# axoloti_micro_modular_002.net
KiCad netlist of a schematic drawn in EAGLE
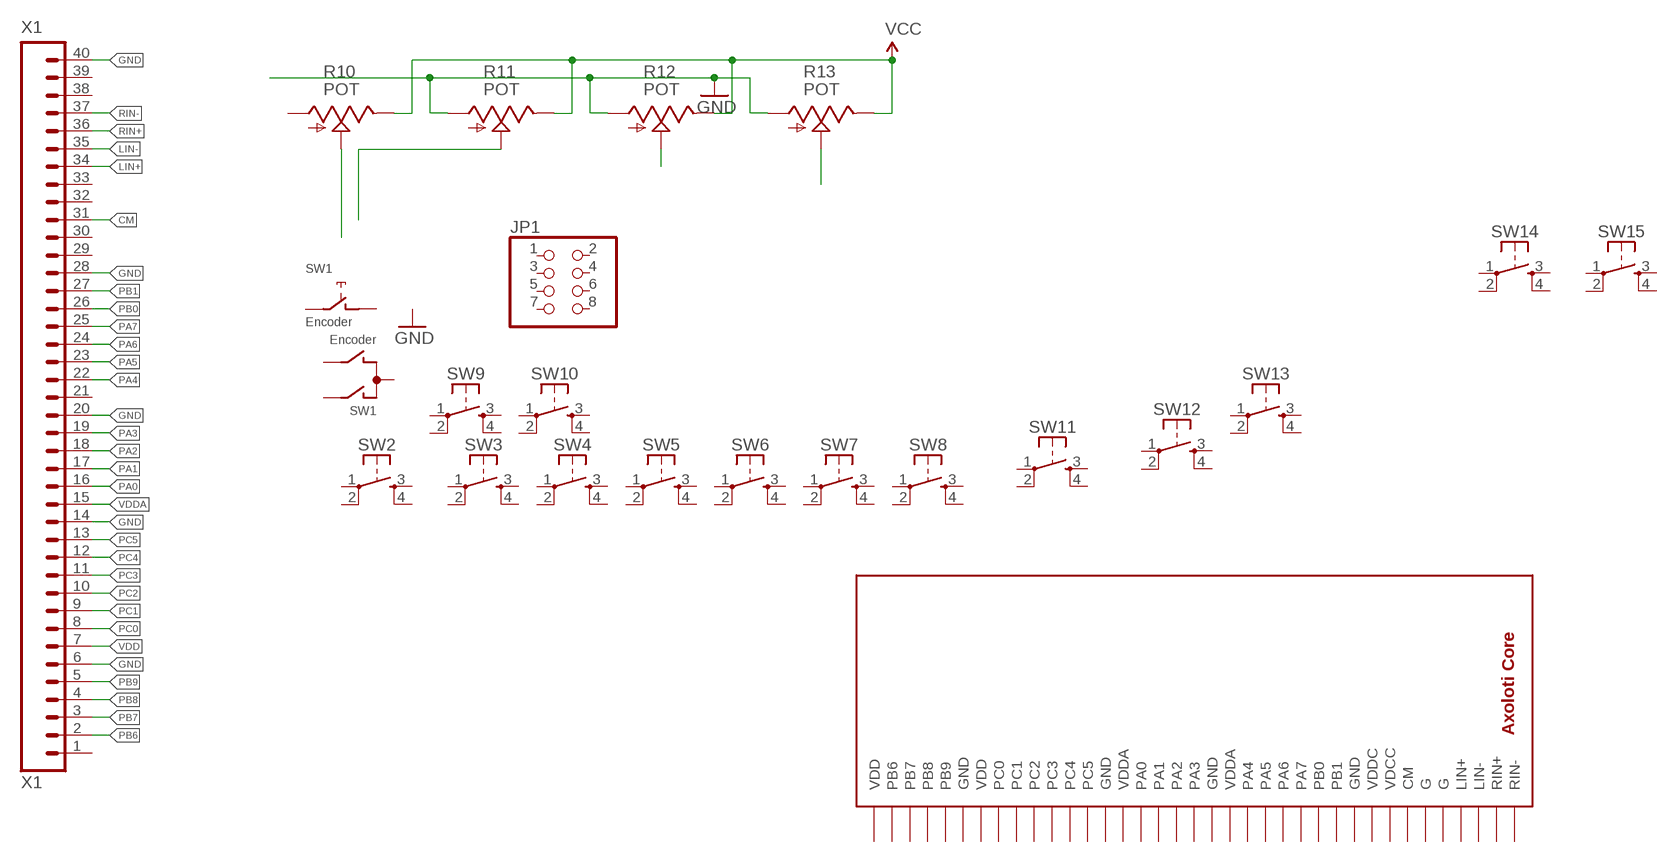
[diagram p0: schematic, sheet 1]

(export (version "E")
  (design (tool "Eeschema 10.0.6"))
  (components
    (comp (ref "JP1")
      (value "PINHD-2X4")
      (footprint "eagle-import:2X04")
      (libsource (lib "eagle-import") (part "PINHD-2X4"))
    )
    (comp (ref "R10")
      (value "POT")
      (footprint "eagle-import:ALPS_POT_SFE")
      (libsource (lib "eagle-import") (part "POT_US"))
    )
    (comp (ref "R11")
      (value "POT")
      (footprint "eagle-import:ALPS_POT_SFE")
      (libsource (lib "eagle-import") (part "POT_US"))
    )
    (comp (ref "R12")
      (value "POT")
      (footprint "eagle-import:ALPS_POT_SFE")
      (libsource (lib "eagle-import") (part "POT_US"))
    )
    (comp (ref "R13")
      (value "POT")
      (footprint "eagle-import:ALPS_POT_SFE")
      (libsource (lib "eagle-import") (part "POT_US"))
    )
    (comp (ref "SW1")
      (value "Encoder")
      (footprint "eagle-import:ALPS_EC12E_SW")
      (libsource (lib "eagle-import") (part "EC12E_SW"))
    )
    (comp (ref "SW2")
      (value "SW-TACTILE-6X6")
      (footprint "eagle-import:SW6X6")
      (libsource (lib "eagle-import") (part "SW-TACTILE-6X6"))
    )
    (comp (ref "SW3")
      (value "SW-TACTILE-6X6")
      (footprint "eagle-import:SW6X6")
      (libsource (lib "eagle-import") (part "SW-TACTILE-6X6"))
    )
    (comp (ref "SW4")
      (value "SW-TACTILE-6X6")
      (footprint "eagle-import:SW6X6")
      (libsource (lib "eagle-import") (part "SW-TACTILE-6X6"))
    )
    (comp (ref "SW5")
      (value "SW-TACTILE-6X6")
      (footprint "eagle-import:SW6X6")
      (libsource (lib "eagle-import") (part "SW-TACTILE-6X6"))
    )
    (comp (ref "SW6")
      (value "SW-TACTILE-6X6")
      (footprint "eagle-import:SW6X6")
      (libsource (lib "eagle-import") (part "SW-TACTILE-6X6"))
    )
    (comp (ref "SW7")
      (value "SW-TACTILE-6X6")
      (footprint "eagle-import:SW6X6")
      (libsource (lib "eagle-import") (part "SW-TACTILE-6X6"))
    )
    (comp (ref "SW8")
      (value "SW-TACTILE-6X6")
      (footprint "eagle-import:SW6X6")
      (libsource (lib "eagle-import") (part "SW-TACTILE-6X6"))
    )
    (comp (ref "SW9")
      (value "SW-TACTILE-6X6")
      (footprint "eagle-import:SW6X6")
      (libsource (lib "eagle-import") (part "SW-TACTILE-6X6"))
    )
    (comp (ref "SW10")
      (value "SW-TACTILE-6X6")
      (footprint "eagle-import:SW6X6")
      (libsource (lib "eagle-import") (part "SW-TACTILE-6X6"))
    )
    (comp (ref "SW11")
      (value "SW-TACTILE-6X6")
      (footprint "eagle-import:SW6X6")
      (libsource (lib "eagle-import") (part "SW-TACTILE-6X6"))
    )
    (comp (ref "SW12")
      (value "SW-TACTILE-6X6")
      (footprint "eagle-import:SW6X6")
      (libsource (lib "eagle-import") (part "SW-TACTILE-6X6"))
    )
    (comp (ref "SW13")
      (value "SW-TACTILE-6X6")
      (footprint "eagle-import:SW6X6")
      (libsource (lib "eagle-import") (part "SW-TACTILE-6X6"))
    )
    (comp (ref "SW14")
      (value "SW-TACTILE-6X6")
      (footprint "eagle-import:SW6X6")
      (libsource (lib "eagle-import") (part "SW-TACTILE-6X6"))
    )
    (comp (ref "SW15")
      (value "SW-TACTILE-6X6")
      (footprint "eagle-import:SW6X6")
      (libsource (lib "eagle-import") (part "SW-TACTILE-6X6"))
    )
    (comp (ref "U$1")
      (value "AXOLOTI_SHIELD_CUTOUT")
      (footprint "eagle-import:AXOLOTI_SHIELD_CUTOUT")
      (libsource (lib "eagle-import") (part "AXOLOTI_SHIELD_CUTOUT"))
    )
    (comp (ref "X1")
      (value "X1")
      (footprint "eagle-import:1X40")
      (libsource (lib "eagle-import") (part "M40"))
    )
  )
  (nets
    (net (code "1") (name "CM") (class "Default")
      (node (ref "X1") (pin "31") (pinfunction "31_31") (pintype "passive"))
    )
    (net (code "2") (name "GND") (class "Default")
      (node (ref "R11") (pin "P$3") (pinfunction "A_P$3") (pintype "passive"))
      (node (ref "R12") (pin "P$3") (pinfunction "A_P$3") (pintype "passive"))
      (node (ref "R13") (pin "P$3") (pinfunction "A_P$3") (pintype "passive"))
      (node (ref "X1") (pin "14") (pinfunction "14_14") (pintype "passive"))
      (node (ref "X1") (pin "20") (pinfunction "20_20") (pintype "passive"))
      (node (ref "X1") (pin "28") (pinfunction "28_28") (pintype "passive"))
      (node (ref "X1") (pin "40") (pinfunction "40_40") (pintype "passive"))
      (node (ref "X1") (pin "6") (pinfunction "6_6") (pintype "passive"))
    )
    (net (code "3") (name "LIN+") (class "Default")
      (node (ref "X1") (pin "34") (pinfunction "34_34") (pintype "passive"))
    )
    (net (code "4") (name "LIN-") (class "Default")
      (node (ref "X1") (pin "35") (pinfunction "35_35") (pintype "passive"))
    )
    (net (code "5") (name "PA0") (class "Default")
      (node (ref "X1") (pin "16") (pinfunction "16_16") (pintype "passive"))
    )
    (net (code "6") (name "PA1") (class "Default")
      (node (ref "X1") (pin "17") (pinfunction "17_17") (pintype "passive"))
    )
    (net (code "7") (name "PA2") (class "Default")
      (node (ref "X1") (pin "18") (pinfunction "18_18") (pintype "passive"))
    )
    (net (code "8") (name "PA3") (class "Default")
      (node (ref "X1") (pin "19") (pinfunction "19_19") (pintype "passive"))
    )
    (net (code "9") (name "PA4") (class "Default")
      (node (ref "X1") (pin "22") (pinfunction "22_22") (pintype "passive"))
    )
    (net (code "10") (name "PA5") (class "Default")
      (node (ref "X1") (pin "23") (pinfunction "23_23") (pintype "passive"))
    )
    (net (code "11") (name "PA6") (class "Default")
      (node (ref "X1") (pin "24") (pinfunction "24_24") (pintype "passive"))
    )
    (net (code "12") (name "PA7") (class "Default")
      (node (ref "X1") (pin "25") (pinfunction "25_25") (pintype "passive"))
    )
    (net (code "13") (name "PB0") (class "Default")
      (node (ref "X1") (pin "26") (pinfunction "26_26") (pintype "passive"))
    )
    (net (code "14") (name "PB1") (class "Default")
      (node (ref "X1") (pin "27") (pinfunction "27_27") (pintype "passive"))
    )
    (net (code "15") (name "PB6") (class "Default")
      (node (ref "X1") (pin "2") (pinfunction "2_2") (pintype "passive"))
    )
    (net (code "16") (name "PB7") (class "Default")
      (node (ref "X1") (pin "3") (pinfunction "3_3") (pintype "passive"))
    )
    (net (code "17") (name "PB8") (class "Default")
      (node (ref "X1") (pin "4") (pinfunction "4_4") (pintype "passive"))
    )
    (net (code "18") (name "PB9") (class "Default")
      (node (ref "X1") (pin "5") (pinfunction "5_5") (pintype "passive"))
    )
    (net (code "19") (name "PC0") (class "Default")
      (node (ref "X1") (pin "8") (pinfunction "8_8") (pintype "passive"))
    )
    (net (code "20") (name "PC1") (class "Default")
      (node (ref "X1") (pin "9") (pinfunction "9_9") (pintype "passive"))
    )
    (net (code "21") (name "PC2") (class "Default")
      (node (ref "X1") (pin "10") (pinfunction "10_10") (pintype "passive"))
    )
    (net (code "22") (name "PC3") (class "Default")
      (node (ref "X1") (pin "11") (pinfunction "11_11") (pintype "passive"))
    )
    (net (code "23") (name "PC4") (class "Default")
      (node (ref "X1") (pin "12") (pinfunction "12_12") (pintype "passive"))
    )
    (net (code "24") (name "PC5") (class "Default")
      (node (ref "X1") (pin "13") (pinfunction "13_13") (pintype "passive"))
    )
    (net (code "25") (name "RIN+") (class "Default")
      (node (ref "X1") (pin "36") (pinfunction "36_36") (pintype "passive"))
    )
    (net (code "26") (name "RIN-") (class "Default")
      (node (ref "X1") (pin "37") (pinfunction "37_37") (pintype "passive"))
    )
    (net (code "27") (name "VCC") (class "Default")
      (node (ref "R10") (pin "P$1") (pinfunction "E_P$1") (pintype "passive"))
      (node (ref "R11") (pin "P$1") (pinfunction "E_P$1") (pintype "passive"))
      (node (ref "R12") (pin "P$1") (pinfunction "E_P$1") (pintype "passive"))
      (node (ref "R13") (pin "P$1") (pinfunction "E_P$1") (pintype "passive"))
    )
    (net (code "28") (name "VDD") (class "Default")
      (node (ref "X1") (pin "7") (pinfunction "7_7") (pintype "passive"))
    )
    (net (code "29") (name "VDDA") (class "Default")
      (node (ref "X1") (pin "15") (pinfunction "15_15") (pintype "passive"))
    )
    (net (code "30") (name "unconnected-(JP1-Pad1)") (class "Default")
      (node (ref "JP1") (pin "1") (pinfunction "1_1") (pintype "passive"))
    )
    (net (code "31") (name "unconnected-(JP1-Pad2)") (class "Default")
      (node (ref "JP1") (pin "2") (pinfunction "2_2") (pintype "passive"))
    )
    (net (code "32") (name "unconnected-(JP1-Pad3)") (class "Default")
      (node (ref "JP1") (pin "3") (pinfunction "3_3") (pintype "passive"))
    )
    (net (code "33") (name "unconnected-(JP1-Pad4)") (class "Default")
      (node (ref "JP1") (pin "4") (pinfunction "4_4") (pintype "passive"))
    )
    (net (code "34") (name "unconnected-(JP1-Pad5)") (class "Default")
      (node (ref "JP1") (pin "5") (pinfunction "5_5") (pintype "passive"))
    )
    (net (code "35") (name "unconnected-(JP1-Pad6)") (class "Default")
      (node (ref "JP1") (pin "6") (pinfunction "6_6") (pintype "passive"))
    )
    (net (code "36") (name "unconnected-(JP1-Pad7)") (class "Default")
      (node (ref "JP1") (pin "7") (pinfunction "7_7") (pintype "passive"))
    )
    (net (code "37") (name "unconnected-(JP1-Pad8)") (class "Default")
      (node (ref "JP1") (pin "8") (pinfunction "8_8") (pintype "passive"))
    )
    (net (code "38") (name "unconnected-(R10-A-PadP$3)") (class "Default")
      (node (ref "R10") (pin "P$3") (pinfunction "A_P$3") (pintype "passive"))
    )
    (net (code "39") (name "unconnected-(R10-S-PadP$2)") (class "Default")
      (node (ref "R10") (pin "P$2") (pinfunction "S_P$2") (pintype "passive"))
    )
    (net (code "40") (name "unconnected-(R11-S-PadP$2)") (class "Default")
      (node (ref "R11") (pin "P$2") (pinfunction "S_P$2") (pintype "passive"))
    )
    (net (code "41") (name "unconnected-(R12-S-PadP$2)") (class "Default")
      (node (ref "R12") (pin "P$2") (pinfunction "S_P$2") (pintype "passive"))
    )
    (net (code "42") (name "unconnected-(R13-S-PadP$2)") (class "Default")
      (node (ref "R13") (pin "P$2") (pinfunction "S_P$2") (pintype "passive"))
    )
    (net (code "43") (name "unconnected-(SW1-PadA)") (class "Default")
      (node (ref "SW1") (pin "A") (pinfunction "A_A") (pintype "passive"))
    )
    (net (code "44") (name "unconnected-(SW1-PadB)") (class "Default")
      (node (ref "SW1") (pin "B") (pinfunction "B_B") (pintype "passive"))
    )
    (net (code "45") (name "unconnected-(SW1-PadC)") (class "Default")
      (node (ref "SW1") (pin "C") (pinfunction "C_C") (pintype "passive"))
    )
    (net (code "46") (name "unconnected-(SW1B-1-PadD)") (class "Default")
      (node (ref "SW1") (pin "D") (pinfunction "1_D") (pintype "passive"))
    )
    (net (code "47") (name "unconnected-(SW1B-2-PadE)") (class "Default")
      (node (ref "SW1") (pin "E") (pinfunction "2_E") (pintype "passive"))
    )
    (net (code "48") (name "unconnected-(SW2-P1-Pad1)") (class "Default")
      (node (ref "SW2") (pin "1") (pinfunction "P1_1") (pintype "passive"))
    )
    (net (code "49") (name "unconnected-(SW2-P2-Pad2)") (class "Default")
      (node (ref "SW2") (pin "2") (pinfunction "P2_2") (pintype "passive"))
    )
    (net (code "50") (name "unconnected-(SW2-S1-Pad3)") (class "Default")
      (node (ref "SW2") (pin "3") (pinfunction "S1_3") (pintype "passive"))
    )
    (net (code "51") (name "unconnected-(SW2-S2-Pad4)") (class "Default")
      (node (ref "SW2") (pin "4") (pinfunction "S2_4") (pintype "passive"))
    )
    (net (code "52") (name "unconnected-(SW3-P1-Pad1)") (class "Default")
      (node (ref "SW3") (pin "1") (pinfunction "P1_1") (pintype "passive"))
    )
    (net (code "53") (name "unconnected-(SW3-P2-Pad2)") (class "Default")
      (node (ref "SW3") (pin "2") (pinfunction "P2_2") (pintype "passive"))
    )
    (net (code "54") (name "unconnected-(SW3-S1-Pad3)") (class "Default")
      (node (ref "SW3") (pin "3") (pinfunction "S1_3") (pintype "passive"))
    )
    (net (code "55") (name "unconnected-(SW3-S2-Pad4)") (class "Default")
      (node (ref "SW3") (pin "4") (pinfunction "S2_4") (pintype "passive"))
    )
    (net (code "56") (name "unconnected-(SW4-P1-Pad1)") (class "Default")
      (node (ref "SW4") (pin "1") (pinfunction "P1_1") (pintype "passive"))
    )
    (net (code "57") (name "unconnected-(SW4-P2-Pad2)") (class "Default")
      (node (ref "SW4") (pin "2") (pinfunction "P2_2") (pintype "passive"))
    )
    (net (code "58") (name "unconnected-(SW4-S1-Pad3)") (class "Default")
      (node (ref "SW4") (pin "3") (pinfunction "S1_3") (pintype "passive"))
    )
    (net (code "59") (name "unconnected-(SW4-S2-Pad4)") (class "Default")
      (node (ref "SW4") (pin "4") (pinfunction "S2_4") (pintype "passive"))
    )
    (net (code "60") (name "unconnected-(SW5-P1-Pad1)") (class "Default")
      (node (ref "SW5") (pin "1") (pinfunction "P1_1") (pintype "passive"))
    )
    (net (code "61") (name "unconnected-(SW5-P2-Pad2)") (class "Default")
      (node (ref "SW5") (pin "2") (pinfunction "P2_2") (pintype "passive"))
    )
    (net (code "62") (name "unconnected-(SW5-S1-Pad3)") (class "Default")
      (node (ref "SW5") (pin "3") (pinfunction "S1_3") (pintype "passive"))
    )
    (net (code "63") (name "unconnected-(SW5-S2-Pad4)") (class "Default")
      (node (ref "SW5") (pin "4") (pinfunction "S2_4") (pintype "passive"))
    )
    (net (code "64") (name "unconnected-(SW6-P1-Pad1)") (class "Default")
      (node (ref "SW6") (pin "1") (pinfunction "P1_1") (pintype "passive"))
    )
    (net (code "65") (name "unconnected-(SW6-P2-Pad2)") (class "Default")
      (node (ref "SW6") (pin "2") (pinfunction "P2_2") (pintype "passive"))
    )
    (net (code "66") (name "unconnected-(SW6-S1-Pad3)") (class "Default")
      (node (ref "SW6") (pin "3") (pinfunction "S1_3") (pintype "passive"))
    )
    (net (code "67") (name "unconnected-(SW6-S2-Pad4)") (class "Default")
      (node (ref "SW6") (pin "4") (pinfunction "S2_4") (pintype "passive"))
    )
    (net (code "68") (name "unconnected-(SW7-P1-Pad1)") (class "Default")
      (node (ref "SW7") (pin "1") (pinfunction "P1_1") (pintype "passive"))
    )
    (net (code "69") (name "unconnected-(SW7-P2-Pad2)") (class "Default")
      (node (ref "SW7") (pin "2") (pinfunction "P2_2") (pintype "passive"))
    )
    (net (code "70") (name "unconnected-(SW7-S1-Pad3)") (class "Default")
      (node (ref "SW7") (pin "3") (pinfunction "S1_3") (pintype "passive"))
    )
    (net (code "71") (name "unconnected-(SW7-S2-Pad4)") (class "Default")
      (node (ref "SW7") (pin "4") (pinfunction "S2_4") (pintype "passive"))
    )
    (net (code "72") (name "unconnected-(SW8-P1-Pad1)") (class "Default")
      (node (ref "SW8") (pin "1") (pinfunction "P1_1") (pintype "passive"))
    )
    (net (code "73") (name "unconnected-(SW8-P2-Pad2)") (class "Default")
      (node (ref "SW8") (pin "2") (pinfunction "P2_2") (pintype "passive"))
    )
    (net (code "74") (name "unconnected-(SW8-S1-Pad3)") (class "Default")
      (node (ref "SW8") (pin "3") (pinfunction "S1_3") (pintype "passive"))
    )
    (net (code "75") (name "unconnected-(SW8-S2-Pad4)") (class "Default")
      (node (ref "SW8") (pin "4") (pinfunction "S2_4") (pintype "passive"))
    )
    (net (code "76") (name "unconnected-(SW9-P1-Pad1)") (class "Default")
      (node (ref "SW9") (pin "1") (pinfunction "P1_1") (pintype "passive"))
    )
    (net (code "77") (name "unconnected-(SW9-P2-Pad2)") (class "Default")
      (node (ref "SW9") (pin "2") (pinfunction "P2_2") (pintype "passive"))
    )
    (net (code "78") (name "unconnected-(SW9-S1-Pad3)") (class "Default")
      (node (ref "SW9") (pin "3") (pinfunction "S1_3") (pintype "passive"))
    )
    (net (code "79") (name "unconnected-(SW9-S2-Pad4)") (class "Default")
      (node (ref "SW9") (pin "4") (pinfunction "S2_4") (pintype "passive"))
    )
    (net (code "80") (name "unconnected-(SW10-P1-Pad1)") (class "Default")
      (node (ref "SW10") (pin "1") (pinfunction "P1_1") (pintype "passive"))
    )
    (net (code "81") (name "unconnected-(SW10-P2-Pad2)") (class "Default")
      (node (ref "SW10") (pin "2") (pinfunction "P2_2") (pintype "passive"))
    )
    (net (code "82") (name "unconnected-(SW10-S1-Pad3)") (class "Default")
      (node (ref "SW10") (pin "3") (pinfunction "S1_3") (pintype "passive"))
    )
    (net (code "83") (name "unconnected-(SW10-S2-Pad4)") (class "Default")
      (node (ref "SW10") (pin "4") (pinfunction "S2_4") (pintype "passive"))
    )
    (net (code "84") (name "unconnected-(SW11-P1-Pad1)") (class "Default")
      (node (ref "SW11") (pin "1") (pinfunction "P1_1") (pintype "passive"))
    )
    (net (code "85") (name "unconnected-(SW11-P2-Pad2)") (class "Default")
      (node (ref "SW11") (pin "2") (pinfunction "P2_2") (pintype "passive"))
    )
    (net (code "86") (name "unconnected-(SW11-S1-Pad3)") (class "Default")
      (node (ref "SW11") (pin "3") (pinfunction "S1_3") (pintype "passive"))
    )
    (net (code "87") (name "unconnected-(SW11-S2-Pad4)") (class "Default")
      (node (ref "SW11") (pin "4") (pinfunction "S2_4") (pintype "passive"))
    )
    (net (code "88") (name "unconnected-(SW12-P1-Pad1)") (class "Default")
      (node (ref "SW12") (pin "1") (pinfunction "P1_1") (pintype "passive"))
    )
    (net (code "89") (name "unconnected-(SW12-P2-Pad2)") (class "Default")
      (node (ref "SW12") (pin "2") (pinfunction "P2_2") (pintype "passive"))
    )
    (net (code "90") (name "unconnected-(SW12-S1-Pad3)") (class "Default")
      (node (ref "SW12") (pin "3") (pinfunction "S1_3") (pintype "passive"))
    )
    (net (code "91") (name "unconnected-(SW12-S2-Pad4)") (class "Default")
      (node (ref "SW12") (pin "4") (pinfunction "S2_4") (pintype "passive"))
    )
    (net (code "92") (name "unconnected-(SW13-P1-Pad1)") (class "Default")
      (node (ref "SW13") (pin "1") (pinfunction "P1_1") (pintype "passive"))
    )
    (net (code "93") (name "unconnected-(SW13-P2-Pad2)") (class "Default")
      (node (ref "SW13") (pin "2") (pinfunction "P2_2") (pintype "passive"))
    )
    (net (code "94") (name "unconnected-(SW13-S1-Pad3)") (class "Default")
      (node (ref "SW13") (pin "3") (pinfunction "S1_3") (pintype "passive"))
    )
    (net (code "95") (name "unconnected-(SW13-S2-Pad4)") (class "Default")
      (node (ref "SW13") (pin "4") (pinfunction "S2_4") (pintype "passive"))
    )
    (net (code "96") (name "unconnected-(SW14-P1-Pad1)") (class "Default")
      (node (ref "SW14") (pin "1") (pinfunction "P1_1") (pintype "passive"))
    )
    (net (code "97") (name "unconnected-(SW14-P2-Pad2)") (class "Default")
      (node (ref "SW14") (pin "2") (pinfunction "P2_2") (pintype "passive"))
    )
    (net (code "98") (name "unconnected-(SW14-S1-Pad3)") (class "Default")
      (node (ref "SW14") (pin "3") (pinfunction "S1_3") (pintype "passive"))
    )
    (net (code "99") (name "unconnected-(SW14-S2-Pad4)") (class "Default")
      (node (ref "SW14") (pin "4") (pinfunction "S2_4") (pintype "passive"))
    )
    (net (code "100") (name "unconnected-(SW15-P1-Pad1)") (class "Default")
      (node (ref "SW15") (pin "1") (pinfunction "P1_1") (pintype "passive"))
    )
    (net (code "101") (name "unconnected-(SW15-P2-Pad2)") (class "Default")
      (node (ref "SW15") (pin "2") (pinfunction "P2_2") (pintype "passive"))
    )
    (net (code "102") (name "unconnected-(SW15-S1-Pad3)") (class "Default")
      (node (ref "SW15") (pin "3") (pinfunction "S1_3") (pintype "passive"))
    )
    (net (code "103") (name "unconnected-(SW15-S2-Pad4)") (class "Default")
      (node (ref "SW15") (pin "4") (pinfunction "S2_4") (pintype "passive"))
    )
    (net (code "104") (name "unconnected-(U$1-G-PadG1)") (class "Default")
      (node (ref "U$1") (pin "G1") (pinfunction "G_G1") (pintype "bidirectional"))
    )
    (net (code "105") (name "unconnected-(U$1-G-PadG2)") (class "Default")
      (node (ref "U$1") (pin "G2") (pinfunction "G_G2") (pintype "bidirectional"))
    )
    (net (code "106") (name "unconnected-(U$1-GND-PadGND1)") (class "Default")
      (node (ref "U$1") (pin "GND1") (pinfunction "GND_GND1") (pintype "bidirectional"))
    )
    (net (code "107") (name "unconnected-(U$1-GND-PadGND2)") (class "Default")
      (node (ref "U$1") (pin "GND2") (pinfunction "GND_GND2") (pintype "bidirectional"))
    )
    (net (code "108") (name "unconnected-(U$1-GND-PadGND3)") (class "Default")
      (node (ref "U$1") (pin "GND3") (pinfunction "GND_GND3") (pintype "bidirectional"))
    )
    (net (code "109") (name "unconnected-(U$1-GND-PadGND4)") (class "Default")
      (node (ref "U$1") (pin "GND4") (pinfunction "GND_GND4") (pintype "bidirectional"))
    )
    (net (code "110") (name "unconnected-(U$1-PadCM)") (class "Default")
      (node (ref "U$1") (pin "CM") (pinfunction "CM_CM") (pintype "bidirectional"))
    )
    (net (code "111") (name "unconnected-(U$1-PadLIN+)") (class "Default")
      (node (ref "U$1") (pin "LIN+") (pinfunction "LIN+_LIN+") (pintype "bidirectional"))
    )
    (net (code "112") (name "unconnected-(U$1-PadLIN-)") (class "Default")
      (node (ref "U$1") (pin "LIN-") (pinfunction "LIN-_LIN-") (pintype "bidirectional"))
    )
    (net (code "113") (name "unconnected-(U$1-PadPA0)") (class "Default")
      (node (ref "U$1") (pin "PA0") (pinfunction "PA0_PA0") (pintype "bidirectional"))
    )
    (net (code "114") (name "unconnected-(U$1-PadPA1)") (class "Default")
      (node (ref "U$1") (pin "PA1") (pinfunction "PA1_PA1") (pintype "bidirectional"))
    )
    (net (code "115") (name "unconnected-(U$1-PadPA2)") (class "Default")
      (node (ref "U$1") (pin "PA2") (pinfunction "PA2_PA2") (pintype "bidirectional"))
    )
    (net (code "116") (name "unconnected-(U$1-PadPA3)") (class "Default")
      (node (ref "U$1") (pin "PA3") (pinfunction "PA3_PA3") (pintype "bidirectional"))
    )
    (net (code "117") (name "unconnected-(U$1-PadPA4)") (class "Default")
      (node (ref "U$1") (pin "PA4") (pinfunction "PA4_PA4") (pintype "bidirectional"))
    )
    (net (code "118") (name "unconnected-(U$1-PadPA5)") (class "Default")
      (node (ref "U$1") (pin "PA5") (pinfunction "PA5_PA5") (pintype "bidirectional"))
    )
    (net (code "119") (name "unconnected-(U$1-PadPA6)") (class "Default")
      (node (ref "U$1") (pin "PA6") (pinfunction "PA6_PA6") (pintype "bidirectional"))
    )
    (net (code "120") (name "unconnected-(U$1-PadPA7)") (class "Default")
      (node (ref "U$1") (pin "PA7") (pinfunction "PA7_PA7") (pintype "bidirectional"))
    )
    (net (code "121") (name "unconnected-(U$1-PadPB0)") (class "Default")
      (node (ref "U$1") (pin "PB0") (pinfunction "PB0_PB0") (pintype "bidirectional"))
    )
    (net (code "122") (name "unconnected-(U$1-PadPB1)") (class "Default")
      (node (ref "U$1") (pin "PB1") (pinfunction "PB1_PB1") (pintype "bidirectional"))
    )
    (net (code "123") (name "unconnected-(U$1-PadPB6)") (class "Default")
      (node (ref "U$1") (pin "PB6") (pinfunction "PB6_PB6") (pintype "bidirectional"))
    )
    (net (code "124") (name "unconnected-(U$1-PadPB7)") (class "Default")
      (node (ref "U$1") (pin "PB7") (pinfunction "PB7_PB7") (pintype "bidirectional"))
    )
    (net (code "125") (name "unconnected-(U$1-PadPB8)") (class "Default")
      (node (ref "U$1") (pin "PB8") (pinfunction "PB8_PB8") (pintype "bidirectional"))
    )
    (net (code "126") (name "unconnected-(U$1-PadPB9)") (class "Default")
      (node (ref "U$1") (pin "PB9") (pinfunction "PB9_PB9") (pintype "bidirectional"))
    )
    (net (code "127") (name "unconnected-(U$1-PadPC0)") (class "Default")
      (node (ref "U$1") (pin "PC0") (pinfunction "PC0_PC0") (pintype "bidirectional"))
    )
    (net (code "128") (name "unconnected-(U$1-PadPC1)") (class "Default")
      (node (ref "U$1") (pin "PC1") (pinfunction "PC1_PC1") (pintype "bidirectional"))
    )
    (net (code "129") (name "unconnected-(U$1-PadPC2)") (class "Default")
      (node (ref "U$1") (pin "PC2") (pinfunction "PC2_PC2") (pintype "bidirectional"))
    )
    (net (code "130") (name "unconnected-(U$1-PadPC3)") (class "Default")
      (node (ref "U$1") (pin "PC3") (pinfunction "PC3_PC3") (pintype "bidirectional"))
    )
    (net (code "131") (name "unconnected-(U$1-PadPC4)") (class "Default")
      (node (ref "U$1") (pin "PC4") (pinfunction "PC4_PC4") (pintype "bidirectional"))
    )
    (net (code "132") (name "unconnected-(U$1-PadPC5)") (class "Default")
      (node (ref "U$1") (pin "PC5") (pinfunction "PC5_PC5") (pintype "bidirectional"))
    )
    (net (code "133") (name "unconnected-(U$1-PadRIN+)") (class "Default")
      (node (ref "U$1") (pin "RIN+") (pinfunction "RIN+_RIN+") (pintype "bidirectional"))
    )
    (net (code "134") (name "unconnected-(U$1-PadRIN-)") (class "Default")
      (node (ref "U$1") (pin "RIN-") (pinfunction "RIN-_RIN-") (pintype "bidirectional"))
    )
    (net (code "135") (name "unconnected-(U$1-VDCC-PadVDDC2)") (class "Default")
      (node (ref "U$1") (pin "VDDC2") (pinfunction "VDCC_VDDC2") (pintype "bidirectional"))
    )
    (net (code "136") (name "unconnected-(U$1-VDD-PadVDD@1)") (class "Default")
      (node (ref "U$1") (pin "VDD@1") (pinfunction "VDD_VDD@1") (pintype "bidirectional"))
    )
    (net (code "137") (name "unconnected-(U$1-VDD-PadVDD@2)") (class "Default")
      (node (ref "U$1") (pin "VDD@2") (pinfunction "VDD_VDD@2") (pintype "bidirectional"))
    )
    (net (code "138") (name "unconnected-(U$1-VDDA-PadVDDA1)") (class "Default")
      (node (ref "U$1") (pin "VDDA1") (pinfunction "VDDA_VDDA1") (pintype "bidirectional"))
    )
    (net (code "139") (name "unconnected-(U$1-VDDA-PadVDDA2)") (class "Default")
      (node (ref "U$1") (pin "VDDA2") (pinfunction "VDDA_VDDA2") (pintype "bidirectional"))
    )
    (net (code "140") (name "unconnected-(U$1-VDDC-PadVDDC1)") (class "Default")
      (node (ref "U$1") (pin "VDDC1") (pinfunction "VDDC_VDDC1") (pintype "bidirectional"))
    )
    (net (code "141") (name "unconnected-(X1-Pad1)") (class "Default")
      (node (ref "X1") (pin "1") (pinfunction "1_1") (pintype "passive"))
    )
    (net (code "142") (name "unconnected-(X1-Pad21)") (class "Default")
      (node (ref "X1") (pin "21") (pinfunction "21_21") (pintype "passive"))
    )
    (net (code "143") (name "unconnected-(X1-Pad29)") (class "Default")
      (node (ref "X1") (pin "29") (pinfunction "29_29") (pintype "passive"))
    )
    (net (code "144") (name "unconnected-(X1-Pad30)") (class "Default")
      (node (ref "X1") (pin "30") (pinfunction "30_30") (pintype "passive"))
    )
    (net (code "145") (name "unconnected-(X1-Pad32)") (class "Default")
      (node (ref "X1") (pin "32") (pinfunction "32_32") (pintype "passive"))
    )
    (net (code "146") (name "unconnected-(X1-Pad33)") (class "Default")
      (node (ref "X1") (pin "33") (pinfunction "33_33") (pintype "passive"))
    )
    (net (code "147") (name "unconnected-(X1-Pad38)") (class "Default")
      (node (ref "X1") (pin "38") (pinfunction "38_38") (pintype "passive"))
    )
    (net (code "148") (name "unconnected-(X1-Pad39)") (class "Default")
      (node (ref "X1") (pin "39") (pinfunction "39_39") (pintype "passive"))
    )
  )
)
